# MCU.net
KiCad netlist of a schematic drawn in Altium Designer
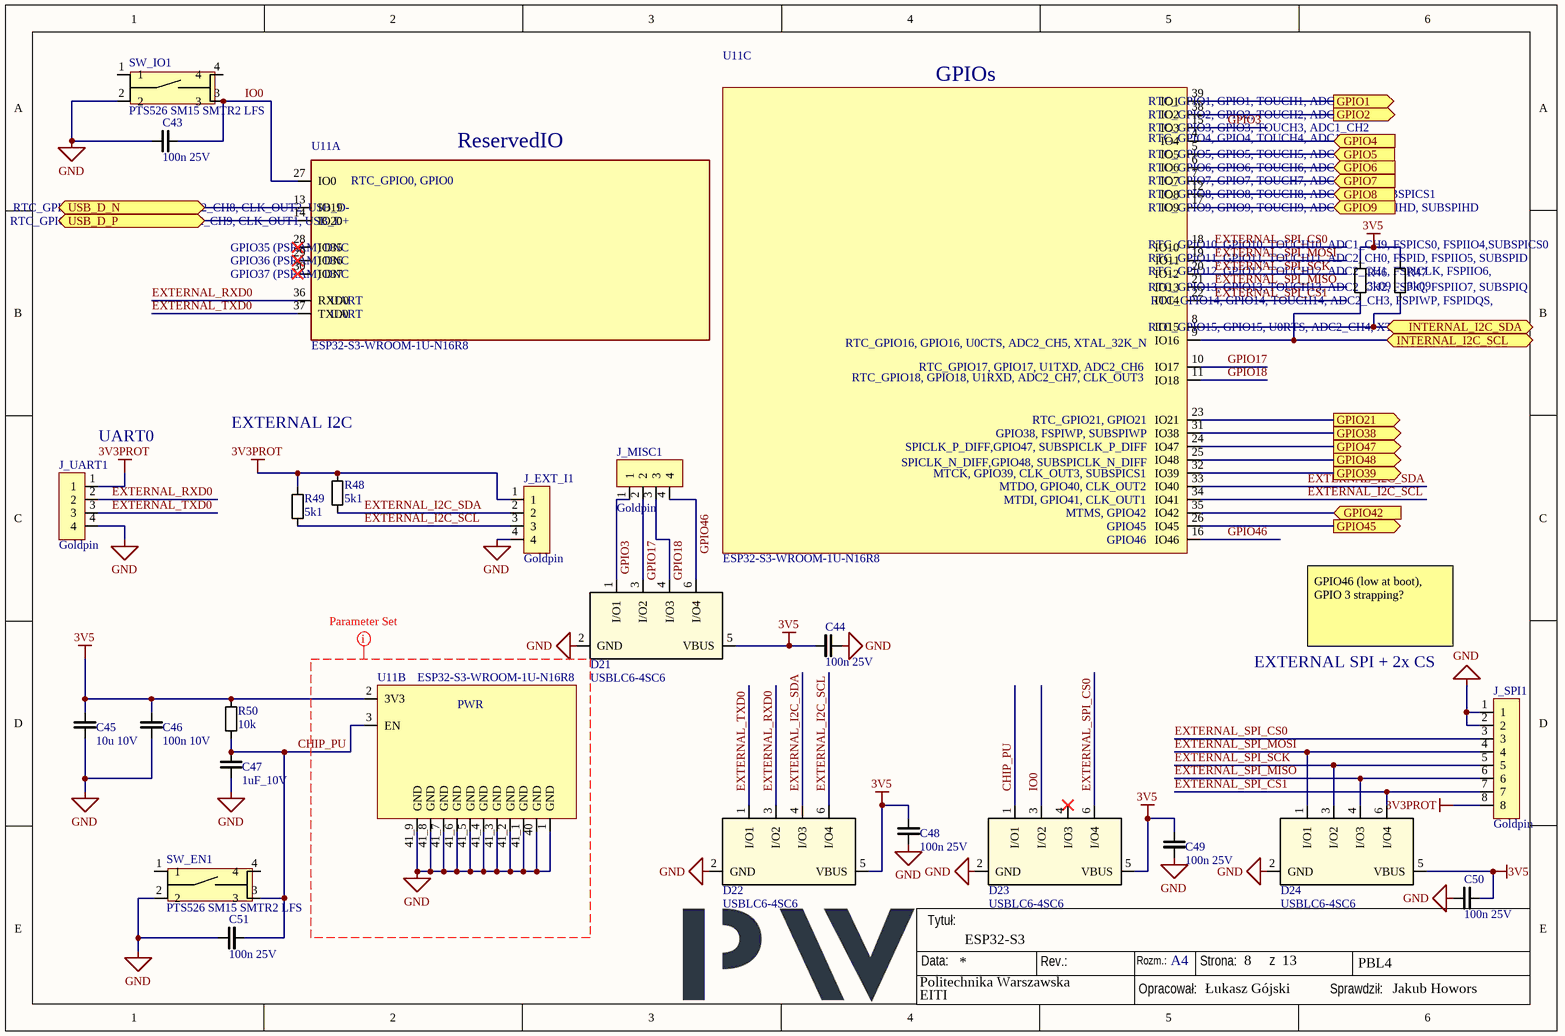
[diagram p0: MCU.SchDoc]

(export (version "E")
  (design (tool "Eeschema 10.0.6"))
  (components
    (comp (ref "C43")
      (value "100n 25V")
      (footprint "C_0603")
      (description "Ceramic capacitor")
      (fields (field (name "VOLTAGE") "25V") (field (name "TOLERANCE") "10%"))
      (libsource (lib "") (part "C_100nF_25V_1"))
    )
    (comp (ref "C44")
      (value "100n 25V")
      (footprint "C_0603")
      (description "Ceramic capacitor")
      (fields (field (name "VOLTAGE") "25V") (field (name "TOLERANCE") "10%"))
      (libsource (lib "Common") (part "C_100nF_25V"))
    )
    (comp (ref "C45")
      (value "10u 10V")
      (footprint "C_0805")
      (description "Ceramic capacitor")
      (fields (field (name "VOLTAGE") "10V") (field (name "TOLERANCE") "10%"))
      (libsource (lib "Common") (part "C_10uF_10V"))
    )
    (comp (ref "C46")
      (value "100n 10V")
      (footprint "C_0603")
      (description "Ceramic capacitor")
      (fields (field (name "VOLTAGE") "10V") (field (name "TOLERANCE") "10%"))
      (libsource (lib "Common") (part "C_100nF_10V"))
    )
    (comp (ref "C47")
      (value "1uF_10V")
      (footprint "C_0603")
      (description "Ceramic capacitor")
      (fields (field (name "VOLTAGE") "10V") (field (name "TOLERANCE") "10%"))
      (libsource (lib "Common") (part "C_1uF_10V"))
    )
    (comp (ref "C48")
      (value "100n 25V")
      (footprint "C_0603")
      (description "Ceramic capacitor")
      (fields (field (name "VOLTAGE") "25V") (field (name "TOLERANCE") "10%"))
      (libsource (lib "") (part "C_100nF_25V_2"))
    )
    (comp (ref "C49")
      (value "100n 25V")
      (footprint "C_0603")
      (description "Ceramic capacitor")
      (fields (field (name "VOLTAGE") "25V") (field (name "TOLERANCE") "10%"))
      (libsource (lib "") (part "C_100nF_25V_2"))
    )
    (comp (ref "C50")
      (value "100n 25V")
      (footprint "C_0603")
      (description "Ceramic capacitor")
      (fields (field (name "VOLTAGE") "25V") (field (name "TOLERANCE") "10%"))
      (libsource (lib "") (part "C_100nF_25V_1"))
    )
    (comp (ref "C51")
      (value "100n 25V")
      (footprint "C_0603")
      (description "Ceramic capacitor")
      (fields (field (name "VOLTAGE") "25V") (field (name "TOLERANCE") "10%"))
      (libsource (lib "") (part "C_100nF_25V_1"))
    )
    (comp (ref "D21")
      (value "USBLC6-4SC6")
      (footprint "SOT23-6L_STM")
      (description "Very low capacitance ESD protection")
      (fields (field (name "MANUFACTURER") "STMicroelectronics"))
      (libsource (lib "Common") (part "USBLC6-4SC6"))
    )
    (comp (ref "D22")
      (value "USBLC6-4SC6")
      (footprint "SOT23-6L_STM")
      (description "Very low capacitance ESD protection")
      (fields (field (name "MANUFACTURER") "STMicroelectronics"))
      (libsource (lib "Common") (part "USBLC6-4SC6"))
    )
    (comp (ref "D23")
      (value "USBLC6-4SC6")
      (footprint "SOT23-6L_STM")
      (description "Very low capacitance ESD protection")
      (fields (field (name "MANUFACTURER") "STMicroelectronics"))
      (libsource (lib "Common") (part "USBLC6-4SC6"))
    )
    (comp (ref "D24")
      (value "USBLC6-4SC6")
      (footprint "SOT23-6L_STM")
      (description "Very low capacitance ESD protection")
      (fields (field (name "MANUFACTURER") "STMicroelectronics"))
      (libsource (lib "Common") (part "USBLC6-4SC6"))
    )
    (comp (ref "J_EXT_I1")
      (value "Goldpin")
      (footprint "goldpin4")
      (description "Goldpin Male 4")
      (libsource (lib "") (part "Goldpin_array_4_1"))
    )
    (comp (ref "J_MISC1")
      (value "Goldpin")
      (footprint "goldpin4")
      (description "Goldpin Male 4")
      (libsource (lib "") (part "Goldpin_array_4_2"))
    )
    (comp (ref "J_SPI1")
      (value "Goldpin")
      (footprint "goldpin8")
      (description "Goldpin Male 8")
      (libsource (lib "Common") (part "Goldpin_array_8"))
    )
    (comp (ref "J_UART1")
      (value "Goldpin")
      (footprint "goldpin4")
      (description "Goldpin Male 4")
      (libsource (lib "Common") (part "Goldpin_array_4"))
    )
    (comp (ref "R46")
      (value "3k09")
      (footprint "R_0603")
      (description "Resistor")
      (fields (field (name "TOLERANCE") "1%") (field (name "POWER") "100mW"))
      (libsource (lib "Common") (part "R_3k09"))
    )
    (comp (ref "R47")
      (value "3k09")
      (footprint "R_0603")
      (description "Resistor")
      (fields (field (name "TOLERANCE") "1%") (field (name "POWER") "100mW"))
      (libsource (lib "Common") (part "R_3k09"))
    )
    (comp (ref "R48")
      (value "5k1")
      (footprint "R_0603")
      (description "Resistor")
      (fields (field (name "TOLERANCE") "1%") (field (name "POWER") "100mW"))
      (libsource (lib "Common") (part "R_5k1"))
    )
    (comp (ref "R49")
      (value "5k1")
      (footprint "R_0603")
      (description "Resistor")
      (fields (field (name "TOLERANCE") "1%") (field (name "POWER") "100mW"))
      (libsource (lib "Common") (part "R_5k1"))
    )
    (comp (ref "R50")
      (value "10k")
      (footprint "R_0603")
      (description "Resistor")
      (fields (field (name "TOLERANCE") "1%") (field (name "POWER") "100mW"))
      (libsource (lib "Common") (part "R_10k"))
    )
    (comp (ref "SW_EN1")
      (value "PTS526 SM15 SMTR2 LFS")
      (footprint "PTS526SK15SMTR2LFS")
      (description "NO button")
      (fields (field (name "MANUFACTURER") "C&K Components"))
      (libsource (lib "MCULib") (part "Button"))
    )
    (comp (ref "SW_IO1")
      (value "PTS526 SM15 SMTR2 LFS")
      (footprint "PTS526SK15SMTR2LFS")
      (description "NO button")
      (fields (field (name "MANUFACTURER") "C&K Components"))
      (libsource (lib "MCULib") (part "Button"))
    )
    (comp (ref "U11")
      (value "ESP32-S3-WROOM-1U-N16R8")
      (footprint "XCVR_ESP32-S3-WROOM-1U-N16R8")
      (fields (field (name "MF") "Espressif Systems"))
      (libsource (lib "MCULib") (part "ESP32-S3-WROOM-1U-N16R8"))
    )
  )
  (nets
    (net (code "1") (name "/CHIP_PU") (class "Default")
      (node (ref "C47") (pin "2") (pinfunction "2_2") (pintype "passive"))
      (node (ref "C51") (pin "2") (pinfunction "2_2") (pintype "passive"))
      (node (ref "D23") (pin "1") (pinfunction "I/O1_1") (pintype "passive"))
      (node (ref "R50") (pin "1") (pinfunction "1_1") (pintype "passive"))
      (node (ref "SW_EN1") (pin "3") (pinfunction "3_3") (pintype "passive"))
      (node (ref "U11") (pin "3") (pinfunction "EN_3") (pintype "passive"))
    )
    (net (code "2") (name "/EXTERNAL_I2C_SCL") (class "Default")
      (node (ref "D22") (pin "6") (pinfunction "I/O4_6") (pintype "passive"))
      (node (ref "J_EXT_I1") (pin "3") (pinfunction "3_3") (pintype "passive"))
      (node (ref "R49") (pin "1") (pinfunction "1_1") (pintype "passive"))
      (node (ref "U11") (pin "34") (pinfunction "IO41_34") (pintype "passive"))
    )
    (net (code "3") (name "/EXTERNAL_I2C_SDA") (class "Default")
      (node (ref "D22") (pin "4") (pinfunction "I/O3_4") (pintype "passive"))
      (node (ref "J_EXT_I1") (pin "2") (pinfunction "2_2") (pintype "passive"))
      (node (ref "R48") (pin "1") (pinfunction "1_1") (pintype "passive"))
      (node (ref "U11") (pin "33") (pinfunction "IO40_33") (pintype "passive"))
    )
    (net (code "4") (name "/EXTERNAL_RXD0") (class "Default")
      (node (ref "D22") (pin "3") (pinfunction "I/O2_3") (pintype "passive"))
      (node (ref "J_UART1") (pin "2") (pinfunction "2_2") (pintype "passive"))
      (node (ref "U11") (pin "36") (pinfunction "RXD0_36") (pintype "passive"))
    )
    (net (code "5") (name "/EXTERNAL_SPI_CS0") (class "Default")
      (node (ref "D23") (pin "6") (pinfunction "I/O4_6") (pintype "passive"))
      (node (ref "J_SPI1") (pin "3") (pinfunction "3_3") (pintype "passive"))
      (node (ref "U11") (pin "18") (pinfunction "IO10_18") (pintype "passive"))
    )
    (net (code "6") (name "/EXTERNAL_SPI_CS1") (class "Default")
      (node (ref "D24") (pin "6") (pinfunction "I/O4_6") (pintype "passive"))
      (node (ref "J_SPI1") (pin "7") (pinfunction "7_7") (pintype "passive"))
      (node (ref "U11") (pin "22") (pinfunction "IO14_22") (pintype "passive"))
    )
    (net (code "7") (name "/EXTERNAL_SPI_MISO") (class "Default")
      (node (ref "D24") (pin "4") (pinfunction "I/O3_4") (pintype "passive"))
      (node (ref "J_SPI1") (pin "6") (pinfunction "6_6") (pintype "passive"))
      (node (ref "U11") (pin "21") (pinfunction "IO13_21") (pintype "passive"))
    )
    (net (code "8") (name "/EXTERNAL_SPI_MOSI") (class "Default")
      (node (ref "D24") (pin "1") (pinfunction "I/O1_1") (pintype "passive"))
      (node (ref "J_SPI1") (pin "4") (pinfunction "4_4") (pintype "passive"))
      (node (ref "U11") (pin "19") (pinfunction "IO11_19") (pintype "passive"))
    )
    (net (code "9") (name "/EXTERNAL_SPI_SCK") (class "Default")
      (node (ref "D24") (pin "3") (pinfunction "I/O2_3") (pintype "passive"))
      (node (ref "J_SPI1") (pin "5") (pinfunction "5_5") (pintype "passive"))
      (node (ref "U11") (pin "20") (pinfunction "IO12_20") (pintype "passive"))
    )
    (net (code "10") (name "/EXTERNAL_TXD0") (class "Default")
      (node (ref "D22") (pin "1") (pinfunction "I/O1_1") (pintype "passive"))
      (node (ref "J_UART1") (pin "3") (pinfunction "3_3") (pintype "passive"))
      (node (ref "U11") (pin "37") (pinfunction "TXD0_37") (pintype "passive"))
    )
    (net (code "11") (name "/GPIO1") (class "Default")
      (node (ref "U11") (pin "39") (pinfunction "IO1_39") (pintype "passive"))
    )
    (net (code "12") (name "/GPIO2") (class "Default")
      (node (ref "U11") (pin "38") (pinfunction "IO2_38") (pintype "passive"))
    )
    (net (code "13") (name "/GPIO3") (class "Default")
      (node (ref "D21") (pin "1") (pinfunction "I/O1_1") (pintype "passive"))
      (node (ref "J_MISC1") (pin "1") (pinfunction "1_1") (pintype "passive"))
      (node (ref "U11") (pin "15") (pinfunction "IO3_15") (pintype "passive"))
    )
    (net (code "14") (name "/GPIO4") (class "Default")
      (node (ref "U11") (pin "4") (pinfunction "IO4_4") (pintype "passive"))
    )
    (net (code "15") (name "/GPIO5") (class "Default")
      (node (ref "U11") (pin "5") (pinfunction "IO5_5") (pintype "passive"))
    )
    (net (code "16") (name "/GPIO6") (class "Default")
      (node (ref "U11") (pin "6") (pinfunction "IO6_6") (pintype "passive"))
    )
    (net (code "17") (name "/GPIO7") (class "Default")
      (node (ref "U11") (pin "7") (pinfunction "IO7_7") (pintype "passive"))
    )
    (net (code "18") (name "/GPIO8") (class "Default")
      (node (ref "U11") (pin "12") (pinfunction "IO8_12") (pintype "passive"))
    )
    (net (code "19") (name "/GPIO9") (class "Default")
      (node (ref "U11") (pin "17") (pinfunction "IO9_17") (pintype "passive"))
    )
    (net (code "20") (name "/GPIO17") (class "Default")
      (node (ref "D21") (pin "3") (pinfunction "I/O2_3") (pintype "passive"))
      (node (ref "J_MISC1") (pin "2") (pinfunction "2_2") (pintype "passive"))
      (node (ref "U11") (pin "10") (pinfunction "IO17_10") (pintype "passive"))
    )
    (net (code "21") (name "/GPIO18") (class "Default")
      (node (ref "D21") (pin "4") (pinfunction "I/O3_4") (pintype "passive"))
      (node (ref "J_MISC1") (pin "3") (pinfunction "3_3") (pintype "passive"))
      (node (ref "U11") (pin "11") (pinfunction "IO18_11") (pintype "passive"))
    )
    (net (code "22") (name "/GPIO21") (class "Default")
      (node (ref "U11") (pin "23") (pinfunction "IO21_23") (pintype "passive"))
    )
    (net (code "23") (name "/GPIO38") (class "Default")
      (node (ref "U11") (pin "31") (pinfunction "IO38_31") (pintype "passive"))
    )
    (net (code "24") (name "/GPIO39") (class "Default")
      (node (ref "U11") (pin "32") (pinfunction "IO39_32") (pintype "passive"))
    )
    (net (code "25") (name "/GPIO42") (class "Default")
      (node (ref "U11") (pin "35") (pinfunction "IO42_35") (pintype "passive"))
    )
    (net (code "26") (name "/GPIO45") (class "Default")
      (node (ref "U11") (pin "26") (pinfunction "IO45_26") (pintype "passive"))
    )
    (net (code "27") (name "/GPIO46") (class "Default")
      (node (ref "D21") (pin "6") (pinfunction "I/O4_6") (pintype "passive"))
      (node (ref "J_MISC1") (pin "4") (pinfunction "4_4") (pintype "passive"))
      (node (ref "U11") (pin "16") (pinfunction "IO46_16") (pintype "passive"))
    )
    (net (code "28") (name "/GPIO47") (class "Default")
      (node (ref "U11") (pin "24") (pinfunction "IO47_24") (pintype "passive"))
    )
    (net (code "29") (name "/GPIO48") (class "Default")
      (node (ref "U11") (pin "25") (pinfunction "IO48_25") (pintype "passive"))
    )
    (net (code "30") (name "/INTERNAL_I2C_SCL") (class "Default")
      (node (ref "R46") (pin "1") (pinfunction "1_1") (pintype "passive"))
      (node (ref "U11") (pin "9") (pinfunction "IO16_9") (pintype "passive"))
    )
    (net (code "31") (name "/INTERNAL_I2C_SDA") (class "Default")
      (node (ref "R47") (pin "1") (pinfunction "1_1") (pintype "passive"))
      (node (ref "U11") (pin "8") (pinfunction "IO15_8") (pintype "passive"))
    )
    (net (code "32") (name "/IO0") (class "Default")
      (node (ref "C43") (pin "2") (pinfunction "2_2") (pintype "passive"))
      (node (ref "D23") (pin "3") (pinfunction "I/O2_3") (pintype "passive"))
      (node (ref "SW_IO1") (pin "3") (pinfunction "3_3") (pintype "passive"))
      (node (ref "U11") (pin "27") (pinfunction "IO0_27") (pintype "passive"))
    )
    (net (code "33") (name "/USB_D_N") (class "Default")
      (node (ref "U11") (pin "13") (pinfunction "IO19_13") (pintype "passive"))
    )
    (net (code "34") (name "/USB_D_P") (class "Default")
      (node (ref "U11") (pin "14") (pinfunction "IO20_14") (pintype "passive"))
    )
    (net (code "35") (name "3V3PROT") (class "Default")
      (node (ref "J_EXT_I1") (pin "1") (pinfunction "1_1") (pintype "passive"))
      (node (ref "J_SPI1") (pin "8") (pinfunction "8_8") (pintype "passive"))
      (node (ref "J_UART1") (pin "1") (pinfunction "1_1") (pintype "passive"))
      (node (ref "R48") (pin "2") (pinfunction "2_2") (pintype "passive"))
      (node (ref "R49") (pin "2") (pinfunction "2_2") (pintype "passive"))
    )
    (net (code "36") (name "3V5") (class "Default")
      (node (ref "C44") (pin "2") (pinfunction "2_2") (pintype "passive"))
      (node (ref "C45") (pin "2") (pinfunction "2_2") (pintype "passive"))
      (node (ref "C46") (pin "2") (pinfunction "2_2") (pintype "passive"))
      (node (ref "C48") (pin "2") (pinfunction "2_2") (pintype "passive"))
      (node (ref "C49") (pin "2") (pinfunction "2_2") (pintype "passive"))
      (node (ref "C50") (pin "2") (pinfunction "2_2") (pintype "passive"))
      (node (ref "D21") (pin "5") (pinfunction "VBUS_5") (pintype "passive"))
      (node (ref "D22") (pin "5") (pinfunction "VBUS_5") (pintype "passive"))
      (node (ref "D23") (pin "5") (pinfunction "VBUS_5") (pintype "passive"))
      (node (ref "D24") (pin "5") (pinfunction "VBUS_5") (pintype "passive"))
      (node (ref "R46") (pin "2") (pinfunction "2_2") (pintype "passive"))
      (node (ref "R47") (pin "2") (pinfunction "2_2") (pintype "passive"))
      (node (ref "R50") (pin "2") (pinfunction "2_2") (pintype "passive"))
      (node (ref "U11") (pin "2") (pinfunction "3V3_2") (pintype "power_in"))
    )
    (net (code "37") (name "GND") (class "Default")
      (node (ref "C43") (pin "1") (pinfunction "1_1") (pintype "passive"))
      (node (ref "C44") (pin "1") (pinfunction "1_1") (pintype "passive"))
      (node (ref "C45") (pin "1") (pinfunction "1_1") (pintype "passive"))
      (node (ref "C46") (pin "1") (pinfunction "1_1") (pintype "passive"))
      (node (ref "C47") (pin "1") (pinfunction "1_1") (pintype "passive"))
      (node (ref "C48") (pin "1") (pinfunction "1_1") (pintype "passive"))
      (node (ref "C49") (pin "1") (pinfunction "1_1") (pintype "passive"))
      (node (ref "C50") (pin "1") (pinfunction "1_1") (pintype "passive"))
      (node (ref "C51") (pin "1") (pinfunction "1_1") (pintype "passive"))
      (node (ref "D21") (pin "2") (pinfunction "GND_2") (pintype "passive"))
      (node (ref "D22") (pin "2") (pinfunction "GND_2") (pintype "passive"))
      (node (ref "D23") (pin "2") (pinfunction "GND_2") (pintype "passive"))
      (node (ref "D24") (pin "2") (pinfunction "GND_2") (pintype "passive"))
      (node (ref "J_EXT_I1") (pin "4") (pinfunction "4_4") (pintype "passive"))
      (node (ref "J_SPI1") (pin "1") (pinfunction "1_1") (pintype "passive"))
      (node (ref "J_SPI1") (pin "2") (pinfunction "2_2") (pintype "passive"))
      (node (ref "J_UART1") (pin "4") (pinfunction "4_4") (pintype "passive"))
      (node (ref "SW_EN1") (pin "2") (pinfunction "2_2") (pintype "passive"))
      (node (ref "SW_IO1") (pin "2") (pinfunction "2_2") (pintype "passive"))
      (node (ref "U11") (pin "1") (pinfunction "GND_1") (pintype "power_in"))
      (node (ref "U11") (pin "40") (pinfunction "GND_40") (pintype "power_in"))
      (node (ref "U11") (pin "41_1") (pinfunction "GND_41_1") (pintype "power_in"))
      (node (ref "U11") (pin "41_2") (pinfunction "GND_41_2") (pintype "power_in"))
      (node (ref "U11") (pin "41_3") (pinfunction "GND_41_3") (pintype "power_in"))
      (node (ref "U11") (pin "41_4") (pinfunction "GND_41_4") (pintype "power_in"))
      (node (ref "U11") (pin "41_5") (pinfunction "GND_41_5") (pintype "power_in"))
      (node (ref "U11") (pin "41_6") (pinfunction "GND_41_6") (pintype "power_in"))
      (node (ref "U11") (pin "41_7") (pinfunction "GND_41_7") (pintype "power_in"))
      (node (ref "U11") (pin "41_8") (pinfunction "GND_41_8") (pintype "power_in"))
      (node (ref "U11") (pin "41_9") (pinfunction "GND_41_9") (pintype "power_in"))
    )
    (net (code "38") (name "unconnected-(D23-I{slash}O3-Pad4)") (class "Default")
      (node (ref "D23") (pin "4") (pinfunction "I/O3_4") (pintype "passive+no_connect"))
    )
    (net (code "39") (name "unconnected-(SW_EN1-Pad1)") (class "Default")
      (node (ref "SW_EN1") (pin "1") (pinfunction "1_1") (pintype "passive"))
    )
    (net (code "40") (name "unconnected-(SW_EN1-Pad4)") (class "Default")
      (node (ref "SW_EN1") (pin "4") (pinfunction "4_4") (pintype "passive"))
    )
    (net (code "41") (name "unconnected-(SW_IO1-Pad1)") (class "Default")
      (node (ref "SW_IO1") (pin "1") (pinfunction "1_1") (pintype "passive"))
    )
    (net (code "42") (name "unconnected-(SW_IO1-Pad4)") (class "Default")
      (node (ref "SW_IO1") (pin "4") (pinfunction "4_4") (pintype "passive"))
    )
    (net (code "43") (name "unconnected-(U11A-IO35-Pad28)") (class "Default")
      (node (ref "U11") (pin "28") (pinfunction "IO35_28") (pintype "passive+no_connect"))
    )
    (net (code "44") (name "unconnected-(U11A-IO36-Pad29)") (class "Default")
      (node (ref "U11") (pin "29") (pinfunction "IO36_29") (pintype "passive+no_connect"))
    )
    (net (code "45") (name "unconnected-(U11A-IO37-Pad30)") (class "Default")
      (node (ref "U11") (pin "30") (pinfunction "IO37_30") (pintype "passive+no_connect"))
    )
  )
)
